# Sheet1.net
KiCad netlist of a schematic drawn in Altium Designer
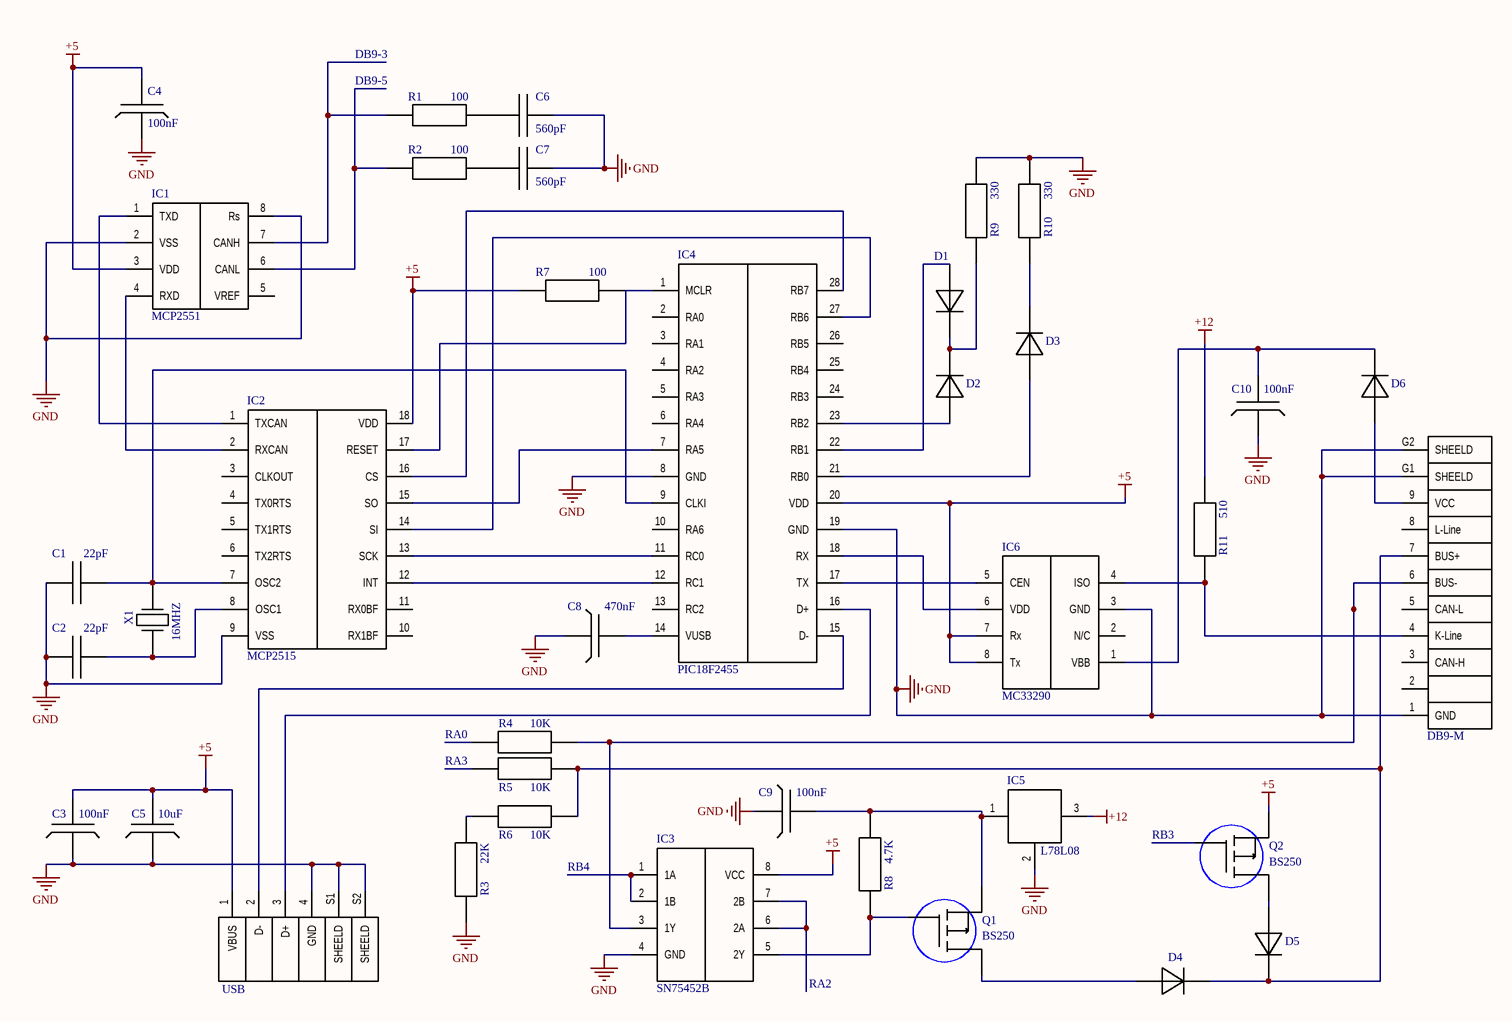
[diagram p0: Sheet1.SchDoc]

(export (version "E")
  (design (tool "Eeschema 10.0.6"))
  (components
    (comp (ref "C1")
      (value "22pF")
      (footprint "Miscellaneous Devices:C0805")
      (description "Capacitor")
      (fields (field (name "PUBLISHER") "Altium Limited"))
      (libsource (lib "PCB_Project") (part "Cap"))
    )
    (comp (ref "C2")
      (value "22pF")
      (footprint "Miscellaneous Devices:C0805")
      (description "Capacitor")
      (fields (field (name "PUBLISHER") "Altium Limited"))
      (libsource (lib "PCB_Project") (part "Cap"))
    )
    (comp (ref "C3")
      (value "100nF")
      (footprint "Miscellaneous Devices:C0805")
      (description "Capacitor with a designated external electrode")
      (fields (field (name "PUBLISHER") "Altium Limited"))
      (libsource (lib "PCB_Project") (part "Cap External"))
    )
    (comp (ref "C4")
      (value "100nF")
      (footprint "Miscellaneous Devices:C0805")
      (description "Capacitor with a designated external electrode")
      (fields (field (name "PUBLISHER") "Altium Limited"))
      (libsource (lib "PCB_Project") (part "Cap External"))
    )
    (comp (ref "C5")
      (value "10uF")
      (footprint "Miscellaneous Devices:C0805")
      (description "Capacitor with a designated external electrode")
      (fields (field (name "PUBLISHER") "Altium Limited"))
      (libsource (lib "PCB_Project") (part "Cap External"))
    )
    (comp (ref "C6")
      (value "560pF")
      (footprint "Miscellaneous Devices:C0805")
      (description "Capacitor")
      (fields (field (name "PUBLISHER") "Altium Limited"))
      (libsource (lib "PCB_Project") (part "Cap"))
    )
    (comp (ref "C7")
      (value "560pF")
      (footprint "Miscellaneous Devices:C0805")
      (description "Capacitor")
      (fields (field (name "PUBLISHER") "Altium Limited"))
      (libsource (lib "PCB_Project") (part "Cap"))
    )
    (comp (ref "C8")
      (value "470nF")
      (footprint "Miscellaneous Devices:C0805")
      (description "Capacitor with a designated external electrode")
      (fields (field (name "PUBLISHER") "Altium Limited"))
      (libsource (lib "PCB_Project") (part "Cap External"))
    )
    (comp (ref "C9")
      (value "100nF")
      (footprint "Miscellaneous Devices:C0805")
      (description "Capacitor with a designated external electrode")
      (fields (field (name "PUBLISHER") "Altium Limited"))
      (libsource (lib "PCB_Project") (part "Cap External"))
    )
    (comp (ref "C10")
      (value "100nF")
      (footprint "Miscellaneous Devices:C0805")
      (description "Capacitor with a designated external electrode")
      (fields (field (name "PUBLISHER") "Altium Limited"))
      (libsource (lib "PCB_Project") (part "Cap External"))
    )
    (comp (ref "D1")
      (value "Diode")
      (footprint "1N4148")
      (description "Default Diode")
      (fields (field (name "PUBLISHER") "Altium Limited"))
      (libsource (lib "PCB_Project") (part "Diode"))
    )
    (comp (ref "D2")
      (value "Diode")
      (footprint "1N4148")
      (description "Default Diode")
      (fields (field (name "PUBLISHER") "Altium Limited"))
      (libsource (lib "PCB_Project") (part "Diode"))
    )
    (comp (ref "D3")
      (value "Diode")
      (footprint "1N4148")
      (description "Default Diode")
      (fields (field (name "PUBLISHER") "Altium Limited"))
      (libsource (lib "PCB_Project") (part "Diode"))
    )
    (comp (ref "D4")
      (value "Diode")
      (footprint "1N4148")
      (description "Default Diode")
      (fields (field (name "PUBLISHER") "Altium Limited"))
      (libsource (lib "PCB_Project") (part "Diode"))
    )
    (comp (ref "D5")
      (value "Diode")
      (footprint "1N4148")
      (description "Default Diode")
      (fields (field (name "PUBLISHER") "Altium Limited"))
      (libsource (lib "PCB_Project") (part "Diode"))
    )
    (comp (ref "D6")
      (value "Diode")
      (footprint "1N4148")
      (description "Default Diode")
      (fields (field (name "PUBLISHER") "Altium Limited"))
      (libsource (lib "PCB_Project") (part "Diode"))
    )
    (comp (ref "IC1")
      (value "MCP2551")
      (footprint "SOIC127P599X175-8N")
      (fields (field (name "MP") "MCP2551-I/SN"))
      (libsource (lib "PCB_Project") (part "MCP2551-I/SN"))
    )
    (comp (ref "IC2")
      (value "MCP2515")
      (footprint "MCP2515")
      (description "CANbus Controller CAN 2.0 SPI Interface 18-SOIC")
      (fields (field (name "MP") "MCP2515-E/SO") (field (name "MF") "Microchip"))
      (libsource (lib "PCB_Project") (part "MCP2515-E/SO"))
    )
    (comp (ref "IC3")
      (value "SN75452B")
      (footprint "SOIC127P599X175-8N")
      (description "30-V Dual output driver with NAND logic inputs")
      (fields (field (name "MF") "Texas Instruments") (field (name "MP") "SN75452BD"))
      (libsource (lib "PCB_Project") (part "SN75452BD"))
    )
    (comp (ref "IC4")
      (value "PIC18F2455")
      (footprint "SOIC-SO28_N")
      (fields (field (name "PUBLISHER") "Altium Limited"))
      (libsource (lib "PCB_Project") (part "PIC18F2455-I/SO"))
    )
    (comp (ref "IC5")
      (value "L78L08")
      (footprint "L78L08")
      (description "Linear Voltage Regulator IC 1 Output 100mA SOT-89-3")
      (fields (field (name "MF") "STMicroelectronics") (field (name "MP") "L78L05ACU"))
      (libsource (lib "PCB_Project") (part "L78L05ACU"))
    )
    (comp (ref "IC6")
      (value "MC33290")
      (footprint "SO08:SO08")
      (fields (field (name "MF") "NXP USA"))
      (libsource (lib "PCB_Project") (part "MC33290"))
    )
    (comp (ref "P1")
      (value "USB")
      (footprint "USB-A1HSW6")
      (description "USB - A Receptacle Connector 4 Position Through Hole, Right Angle")
      (fields (field (name "MP") "USB-A1HSW6"))
      (libsource (lib "PCB_Project") (part "USB-A1HSW6"))
    )
    (comp (ref "P2") (value "DB9-M") (footprint "DB9") (libsource (lib "PCB_Project") (part "DB9-M")))
    (comp (ref "Q1")
      (value "BS250")
      (footprint "BS250FTA")
      (description "P-Channel 45V 90mA (Ta) 330mW (Ta) Surface Mount SOT-23-3")
      (fields (field (name "MF") "Diodes Inc.") (field (name "MP") "BS250FTA"))
      (libsource (lib "PCB_Project") (part "BS250FTA"))
    )
    (comp (ref "Q2")
      (value "BS250")
      (footprint "BS250FTA")
      (description "P-Channel 45V 90mA (Ta) 330mW (Ta) Surface Mount SOT-23-3")
      (fields (field (name "MF") "Diodes Inc.") (field (name "MP") "BS250FTA"))
      (libsource (lib "PCB_Project") (part "BS250FTA"))
    )
    (comp (ref "R1")
      (value "100")
      (footprint "Miscellaneous Devices:J1-0603")
      (description "Resistor")
      (fields (field (name "PUBLISHER") "Altium Limited"))
      (libsource (lib "PCB_Project") (part "Res3"))
    )
    (comp (ref "R2")
      (value "100")
      (footprint "Miscellaneous Devices:J1-0603")
      (description "Resistor")
      (fields (field (name "PUBLISHER") "Altium Limited"))
      (libsource (lib "PCB_Project") (part "Res3"))
    )
    (comp (ref "R3")
      (value "22K")
      (footprint "Miscellaneous Devices:J1-0603")
      (description "Resistor")
      (fields (field (name "PUBLISHER") "Altium Limited"))
      (libsource (lib "PCB_Project") (part "Res3"))
    )
    (comp (ref "R4")
      (value "10K")
      (footprint "Miscellaneous Devices:J1-0603")
      (description "Resistor")
      (fields (field (name "PUBLISHER") "Altium Limited"))
      (libsource (lib "PCB_Project") (part "Res3"))
    )
    (comp (ref "R5")
      (value "10K")
      (footprint "Miscellaneous Devices:J1-0603")
      (description "Resistor")
      (fields (field (name "PUBLISHER") "Altium Limited"))
      (libsource (lib "PCB_Project") (part "Res3"))
    )
    (comp (ref "R6")
      (value "10K")
      (footprint "Miscellaneous Devices:J1-0603")
      (description "Resistor")
      (fields (field (name "PUBLISHER") "Altium Limited"))
      (libsource (lib "PCB_Project") (part "Res3"))
    )
    (comp (ref "R7")
      (value "100")
      (footprint "Miscellaneous Devices:J1-0603")
      (description "Resistor")
      (fields (field (name "PUBLISHER") "Altium Limited"))
      (libsource (lib "PCB_Project") (part "Res3"))
    )
    (comp (ref "R8")
      (value "4.7K")
      (footprint "Miscellaneous Devices:J1-0603")
      (description "Resistor")
      (fields (field (name "PUBLISHER") "Altium Limited"))
      (libsource (lib "PCB_Project") (part "Res3"))
    )
    (comp (ref "R9")
      (value "330")
      (footprint "Miscellaneous Devices:J1-0603")
      (description "Resistor")
      (fields (field (name "PUBLISHER") "Altium Limited"))
      (libsource (lib "PCB_Project") (part "Res3"))
    )
    (comp (ref "R10")
      (value "330")
      (footprint "Miscellaneous Devices:J1-0603")
      (description "Resistor")
      (fields (field (name "PUBLISHER") "Altium Limited"))
      (libsource (lib "PCB_Project") (part "Res3"))
    )
    (comp (ref "R11")
      (value "510")
      (footprint "Miscellaneous Devices:J1-0603")
      (description "Resistor")
      (fields (field (name "PUBLISHER") "Altium Limited"))
      (libsource (lib "PCB_Project") (part "Res3"))
    )
    (comp (ref "X1")
      (value "16MHZ")
      (footprint "X-16.000MHZ-B4")
      (description "16 MHz Â±30ppm Crystal 18pF 40 Ohms HC-49/US")
      (fields (field (name "MP") "ABLS-16.000MHZ-B4") (field (name "MF") "Abracon"))
      (libsource (lib "PCB_Project") (part "ABLS-16.000MHZ-B4"))
    )
  )
  (nets
    (net (code "1") (name "+5") (class "Default")
      (node (ref "C3") (pin "1") (pinfunction "1_1") (pintype "passive"))
      (node (ref "C4") (pin "1") (pinfunction "1_1") (pintype "passive"))
      (node (ref "C5") (pin "1") (pinfunction "1_1") (pintype "passive"))
      (node (ref "IC1") (pin "3") (pinfunction "VDD_3") (pintype "power_in"))
      (node (ref "IC2") (pin "18") (pinfunction "VDD_18") (pintype "passive"))
      (node (ref "IC3") (pin "8") (pinfunction "VCC_8") (pintype "power_in"))
      (node (ref "IC4") (pin "20") (pinfunction "VDD_20") (pintype "power_in"))
      (node (ref "IC6") (pin "7") (pinfunction "Rx_7") (pintype "passive"))
      (node (ref "IC6") (pin "8") (pinfunction "Tx_8") (pintype "passive"))
      (node (ref "P1") (pin "1") (pinfunction "VBUS_1") (pintype "passive"))
      (node (ref "Q2") (pin "2") (pinfunction "S_2") (pintype "passive"))
      (node (ref "R7") (pin "1") (pinfunction "1_1") (pintype "passive"))
    )
    (net (code "2") (name "+12") (class "Default")
      (node (ref "IC5") (pin "3") (pinfunction "IN_3") (pintype "power_in"))
      (node (ref "R11") (pin "2") (pinfunction "2_2") (pintype "passive"))
    )
    (net (code "3") (name "GND") (class "Default")
      (node (ref "C1") (pin "1") (pinfunction "1_1") (pintype "passive"))
      (node (ref "C10") (pin "2") (pinfunction "2_2") (pintype "passive"))
      (node (ref "C2") (pin "1") (pinfunction "1_1") (pintype "passive"))
      (node (ref "C3") (pin "2") (pinfunction "2_2") (pintype "passive"))
      (node (ref "C4") (pin "2") (pinfunction "2_2") (pintype "passive"))
      (node (ref "C5") (pin "2") (pinfunction "2_2") (pintype "passive"))
      (node (ref "C6") (pin "2") (pinfunction "2_2") (pintype "passive"))
      (node (ref "C7") (pin "2") (pinfunction "2_2") (pintype "passive"))
      (node (ref "C8") (pin "2") (pinfunction "2_2") (pintype "passive"))
      (node (ref "C9") (pin "2") (pinfunction "2_2") (pintype "passive"))
      (node (ref "IC1") (pin "2") (pinfunction "VSS_2") (pintype "power_in"))
      (node (ref "IC1") (pin "8") (pinfunction "Rs_8") (pintype "passive"))
      (node (ref "IC2") (pin "9") (pinfunction "VSS_9") (pintype "power_in"))
      (node (ref "IC3") (pin "4") (pinfunction "GND_4") (pintype "power_in"))
      (node (ref "IC4") (pin "19") (pinfunction "GND_19") (pintype "power_in"))
      (node (ref "IC4") (pin "8") (pinfunction "GND_8") (pintype "power_in"))
      (node (ref "IC5") (pin "2") (pinfunction "GND_2") (pintype "power_in"))
      (node (ref "IC6") (pin "3") (pinfunction "GND_3") (pintype "power_in"))
      (node (ref "P1") (pin "4") (pinfunction "GND_4") (pintype "power_in"))
      (node (ref "P1") (pin "S1") (pinfunction "SHEELD_S1") (pintype "passive"))
      (node (ref "P1") (pin "S2") (pinfunction "SHEELD_S2") (pintype "passive"))
      (node (ref "P2") (pin "1") (pinfunction "GND_1") (pintype "passive"))
      (node (ref "P2") (pin "G1") (pinfunction "SHEELD_G1") (pintype "passive"))
      (node (ref "P2") (pin "G2") (pinfunction "SHEELD_G2") (pintype "passive"))
      (node (ref "R10") (pin "2") (pinfunction "2_2") (pintype "passive"))
      (node (ref "R3") (pin "1") (pinfunction "1_1") (pintype "passive"))
      (node (ref "R9") (pin "2") (pinfunction "2_2") (pintype "passive"))
    )
    (net (code "4") (name "Net-(C6-Pad1)") (class "Default")
      (node (ref "C6") (pin "1") (pinfunction "1_1") (pintype "passive"))
      (node (ref "R1") (pin "2") (pinfunction "2_2") (pintype "passive"))
    )
    (net (code "5") (name "Net-(C7-Pad1)") (class "Default")
      (node (ref "C7") (pin "1") (pinfunction "1_1") (pintype "passive"))
      (node (ref "R2") (pin "2") (pinfunction "2_2") (pintype "passive"))
    )
    (net (code "6") (name "Net-(D1-Pad2)") (class "Default")
      (node (ref "D1") (pin "2") (pinfunction "2_2") (pintype "passive"))
      (node (ref "D2") (pin "2") (pinfunction "2_2") (pintype "passive"))
      (node (ref "R9") (pin "1") (pinfunction "1_1") (pintype "passive"))
    )
    (net (code "7") (name "Net-(D3-Pad2)") (class "Default")
      (node (ref "D3") (pin "2") (pinfunction "2_2") (pintype "passive"))
      (node (ref "R10") (pin "1") (pinfunction "1_1") (pintype "passive"))
    )
    (net (code "8") (name "Net-(IC1-CANH)") (class "Default")
      (node (ref "IC1") (pin "7") (pinfunction "CANH_7") (pintype "passive"))
      (node (ref "R1") (pin "1") (pinfunction "1_1") (pintype "passive"))
    )
    (net (code "9") (name "Net-(IC1-CANL)") (class "Default")
      (node (ref "IC1") (pin "6") (pinfunction "CANL_6") (pintype "passive"))
      (node (ref "R2") (pin "1") (pinfunction "1_1") (pintype "passive"))
    )
    (net (code "10") (name "Net-(IC1-RXD)") (class "Default")
      (node (ref "IC1") (pin "4") (pinfunction "RXD_4") (pintype "passive"))
      (node (ref "IC2") (pin "2") (pinfunction "RXCAN_2") (pintype "passive"))
    )
    (net (code "11") (name "Net-(IC1-TXD)") (class "Default")
      (node (ref "IC1") (pin "1") (pinfunction "TXD_1") (pintype "passive"))
      (node (ref "IC2") (pin "1") (pinfunction "TXCAN_1") (pintype "passive"))
    )
    (net (code "12") (name "Net-(IC2-CS)") (class "Default")
      (node (ref "IC2") (pin "16") (pinfunction "CS_16") (pintype "passive"))
      (node (ref "IC4") (pin "28") (pinfunction "RB7_28") (pintype "passive"))
    )
    (net (code "13") (name "Net-(IC2-INT)") (class "Default")
      (node (ref "IC2") (pin "12") (pinfunction "INT_12") (pintype "passive"))
      (node (ref "IC4") (pin "12") (pinfunction "RC1_12") (pintype "passive"))
    )
    (net (code "14") (name "Net-(IC2-OSC1)") (class "Default")
      (node (ref "C2") (pin "2") (pinfunction "2_2") (pintype "passive"))
      (node (ref "IC2") (pin "8") (pinfunction "OSC1_8") (pintype "power_in"))
      (node (ref "X1") (pin "1") (pintype "passive"))
    )
    (net (code "15") (name "Net-(IC2-OSC2)") (class "Default")
      (node (ref "C1") (pin "2") (pinfunction "2_2") (pintype "passive"))
      (node (ref "IC2") (pin "7") (pinfunction "OSC2_7") (pintype "passive"))
      (node (ref "IC4") (pin "9") (pinfunction "CLKI_9") (pintype "passive"))
      (node (ref "X1") (pin "2") (pintype "passive"))
    )
    (net (code "16") (name "Net-(IC2-RESET)") (class "Default")
      (node (ref "IC2") (pin "17") (pinfunction "RESET_17") (pintype "passive"))
      (node (ref "IC4") (pin "1") (pinfunction "MCLR_1") (pintype "passive"))
      (node (ref "R7") (pin "2") (pinfunction "2_2") (pintype "passive"))
    )
    (net (code "17") (name "Net-(IC2-SCK)") (class "Default")
      (node (ref "IC2") (pin "13") (pinfunction "SCK_13") (pintype "passive"))
      (node (ref "IC4") (pin "11") (pinfunction "RC0_11") (pintype "passive"))
    )
    (net (code "18") (name "Net-(IC2-SI)") (class "Default")
      (node (ref "IC2") (pin "14") (pinfunction "SI_14") (pintype "passive"))
      (node (ref "IC4") (pin "27") (pinfunction "RB6_27") (pintype "passive"))
    )
    (net (code "19") (name "Net-(IC2-SO)") (class "Default")
      (node (ref "IC2") (pin "15") (pinfunction "SO_15") (pintype "passive"))
      (node (ref "IC4") (pin "7") (pinfunction "RA5_7") (pintype "passive"))
    )
    (net (code "20") (name "Net-(IC3-1A)") (class "Default")
      (node (ref "IC3") (pin "1") (pinfunction "1A_1") (pintype "passive"))
      (node (ref "IC3") (pin "2") (pinfunction "1B_2") (pintype "passive"))
    )
    (net (code "21") (name "Net-(IC3-1Y)") (class "Default")
      (node (ref "IC3") (pin "3") (pinfunction "1Y_3") (pintype "passive"))
      (node (ref "P2") (pin "6") (pinfunction "BUS-_6") (pintype "passive"))
      (node (ref "R4") (pin "2") (pinfunction "2_2") (pintype "passive"))
    )
    (net (code "22") (name "Net-(IC3-2A)") (class "Default")
      (node (ref "IC3") (pin "6") (pinfunction "2A_6") (pintype "passive"))
      (node (ref "IC3") (pin "7") (pinfunction "2B_7") (pintype "passive"))
    )
    (net (code "23") (name "Net-(IC3-2Y)") (class "Default")
      (node (ref "IC3") (pin "5") (pinfunction "2Y_5") (pintype "passive"))
      (node (ref "Q1") (pin "1") (pinfunction "G_1") (pintype "passive"))
      (node (ref "R8") (pin "1") (pinfunction "1_1") (pintype "passive"))
    )
    (net (code "24") (name "Net-(IC4-D+)") (class "Default")
      (node (ref "IC4") (pin "16") (pinfunction "D+_16") (pintype "passive"))
      (node (ref "P1") (pin "3") (pinfunction "D+_3") (pintype "passive"))
    )
    (net (code "25") (name "Net-(IC4-D-)") (class "Default")
      (node (ref "IC4") (pin "15") (pinfunction "D-_15") (pintype "passive"))
      (node (ref "P1") (pin "2") (pinfunction "D-_2") (pintype "passive"))
    )
    (net (code "26") (name "Net-(IC4-RB0)") (class "Default")
      (node (ref "D3") (pin "1") (pinfunction "1_1") (pintype "passive"))
      (node (ref "IC4") (pin "21") (pinfunction "RB0_21") (pintype "passive"))
    )
    (net (code "27") (name "Net-(IC4-RB1)") (class "Default")
      (node (ref "D1") (pin "1") (pinfunction "1_1") (pintype "passive"))
      (node (ref "IC4") (pin "22") (pinfunction "RB1_22") (pintype "passive"))
    )
    (net (code "28") (name "Net-(IC4-RB2)") (class "Default")
      (node (ref "D2") (pin "1") (pinfunction "1_1") (pintype "passive"))
      (node (ref "IC4") (pin "23") (pinfunction "RB2_23") (pintype "passive"))
    )
    (net (code "29") (name "Net-(IC4-RX)") (class "Default")
      (node (ref "IC4") (pin "18") (pinfunction "RX_18") (pintype "passive"))
      (node (ref "IC6") (pin "6") (pinfunction "VDD_6") (pintype "power_in"))
    )
    (net (code "30") (name "Net-(IC4-TX)") (class "Default")
      (node (ref "IC4") (pin "17") (pinfunction "TX_17") (pintype "passive"))
      (node (ref "IC6") (pin "5") (pinfunction "CEN_5") (pintype "passive"))
    )
    (net (code "31") (name "Net-(IC4-VUSB)") (class "Default")
      (node (ref "C8") (pin "1") (pinfunction "1_1") (pintype "passive"))
      (node (ref "IC4") (pin "14") (pinfunction "VUSB_14") (pintype "passive"))
    )
    (net (code "32") (name "Net-(IC5-OUT)") (class "Default")
      (node (ref "C9") (pin "1") (pinfunction "1_1") (pintype "passive"))
      (node (ref "IC5") (pin "1") (pinfunction "OUT_1") (pintype "power_in"))
      (node (ref "Q1") (pin "2") (pinfunction "S_2") (pintype "passive"))
      (node (ref "R8") (pin "2") (pinfunction "2_2") (pintype "passive"))
    )
    (net (code "33") (name "Net-(IC6-ISO)") (class "Default")
      (node (ref "IC6") (pin "4") (pinfunction "ISO_4") (pintype "passive"))
      (node (ref "P2") (pin "4") (pinfunction "K-Line_4") (pintype "passive"))
      (node (ref "R11") (pin "1") (pinfunction "1_1") (pintype "passive"))
    )
    (net (code "34") (name "Net-(IC6-VBB)") (class "Default")
      (node (ref "C10") (pin "1") (pinfunction "1_1") (pintype "passive"))
      (node (ref "D6") (pin "2") (pinfunction "2_2") (pintype "passive"))
      (node (ref "IC6") (pin "1") (pinfunction "VBB_1") (pintype "passive"))
    )
    (net (code "35") (name "Net-(P2-BUS+)") (class "Default")
      (node (ref "D4") (pin "2") (pinfunction "2_2") (pintype "passive"))
      (node (ref "D5") (pin "2") (pinfunction "2_2") (pintype "passive"))
      (node (ref "P2") (pin "7") (pinfunction "BUS+_7") (pintype "passive"))
      (node (ref "R5") (pin "2") (pinfunction "2_2") (pintype "passive"))
      (node (ref "R6") (pin "2") (pinfunction "2_2") (pintype "passive"))
    )
    (net (code "36") (name "Net-(P2-VCC)") (class "Default")
      (node (ref "D6") (pin "1") (pinfunction "1_1") (pintype "passive"))
      (node (ref "P2") (pin "9") (pinfunction "VCC_9") (pintype "passive"))
    )
    (net (code "37") (name "Net-(Q1-D)") (class "Default")
      (node (ref "D4") (pin "1") (pinfunction "1_1") (pintype "passive"))
      (node (ref "Q1") (pin "3") (pinfunction "D_3") (pintype "passive"))
    )
    (net (code "38") (name "Net-(Q2-D)") (class "Default")
      (node (ref "D5") (pin "1") (pinfunction "1_1") (pintype "passive"))
      (node (ref "Q2") (pin "3") (pinfunction "D_3") (pintype "passive"))
    )
    (net (code "39") (name "Net-(R3-Pad2)") (class "Default")
      (node (ref "R3") (pin "2") (pinfunction "2_2") (pintype "passive"))
      (node (ref "R6") (pin "1") (pinfunction "1_1") (pintype "passive"))
    )
    (net (code "40") (name "unconnected-(IC1-VREF-Pad5)") (class "Default")
      (node (ref "IC1") (pin "5") (pinfunction "VREF_5") (pintype "passive"))
    )
    (net (code "41") (name "unconnected-(IC2-CLKOUT-Pad3)") (class "Default")
      (node (ref "IC2") (pin "3") (pinfunction "CLKOUT_3") (pintype "passive"))
    )
    (net (code "42") (name "unconnected-(IC2-RX0BF-Pad11)") (class "Default")
      (node (ref "IC2") (pin "11") (pinfunction "RX0BF_11") (pintype "passive"))
    )
    (net (code "43") (name "unconnected-(IC2-RX1BF-Pad10)") (class "Default")
      (node (ref "IC2") (pin "10") (pinfunction "RX1BF_10") (pintype "passive"))
    )
    (net (code "44") (name "unconnected-(IC2-TX0RTS-Pad4)") (class "Default")
      (node (ref "IC2") (pin "4") (pinfunction "TX0RTS_4") (pintype "passive"))
    )
    (net (code "45") (name "unconnected-(IC2-TX1RTS-Pad5)") (class "Default")
      (node (ref "IC2") (pin "5") (pinfunction "TX1RTS_5") (pintype "passive"))
    )
    (net (code "46") (name "unconnected-(IC2-TX2RTS-Pad6)") (class "Default")
      (node (ref "IC2") (pin "6") (pinfunction "TX2RTS_6") (pintype "passive"))
    )
    (net (code "47") (name "unconnected-(IC4-RA0-Pad2)") (class "Default")
      (node (ref "IC4") (pin "2") (pinfunction "RA0_2") (pintype "passive"))
    )
    (net (code "48") (name "unconnected-(IC4-RA1-Pad3)") (class "Default")
      (node (ref "IC4") (pin "3") (pinfunction "RA1_3") (pintype "passive"))
    )
    (net (code "49") (name "unconnected-(IC4-RA2-Pad4)") (class "Default")
      (node (ref "IC4") (pin "4") (pinfunction "RA2_4") (pintype "passive"))
    )
    (net (code "50") (name "unconnected-(IC4-RA3-Pad5)") (class "Default")
      (node (ref "IC4") (pin "5") (pinfunction "RA3_5") (pintype "passive"))
    )
    (net (code "51") (name "unconnected-(IC4-RA4-Pad6)") (class "Default")
      (node (ref "IC4") (pin "6") (pinfunction "RA4_6") (pintype "passive"))
    )
    (net (code "52") (name "unconnected-(IC4-RA6-Pad10)") (class "Default")
      (node (ref "IC4") (pin "10") (pinfunction "RA6_10") (pintype "passive"))
    )
    (net (code "53") (name "unconnected-(IC4-RB3-Pad24)") (class "Default")
      (node (ref "IC4") (pin "24") (pinfunction "RB3_24") (pintype "passive"))
    )
    (net (code "54") (name "unconnected-(IC4-RB4-Pad25)") (class "Default")
      (node (ref "IC4") (pin "25") (pinfunction "RB4_25") (pintype "passive"))
    )
    (net (code "55") (name "unconnected-(IC4-RB5-Pad26)") (class "Default")
      (node (ref "IC4") (pin "26") (pinfunction "RB5_26") (pintype "passive"))
    )
    (net (code "56") (name "unconnected-(IC4-RC2-Pad13)") (class "Default")
      (node (ref "IC4") (pin "13") (pinfunction "RC2_13") (pintype "passive"))
    )
    (net (code "57") (name "unconnected-(IC6-N{slash}C-Pad2)") (class "Default")
      (node (ref "IC6") (pin "2") (pinfunction "N/C_2") (pintype "passive"))
    )
    (net (code "58") (name "unconnected-(P2-CAN-H-Pad3)") (class "Default")
      (node (ref "P2") (pin "3") (pinfunction "CAN-H_3") (pintype "passive"))
    )
    (net (code "59") (name "unconnected-(P2-CAN-L-Pad5)") (class "Default")
      (node (ref "P2") (pin "5") (pinfunction "CAN-L_5") (pintype "passive"))
    )
    (net (code "60") (name "unconnected-(P2-L-Line-Pad8)") (class "Default")
      (node (ref "P2") (pin "8") (pinfunction "L-Line_8") (pintype "passive"))
    )
    (net (code "61") (name "unconnected-(P2-Pad2)") (class "Default")
      (node (ref "P2") (pin "2") (pintype "passive"))
    )
    (net (code "62") (name "unconnected-(Q2-G-Pad1)") (class "Default")
      (node (ref "Q2") (pin "1") (pinfunction "G_1") (pintype "passive"))
    )
    (net (code "63") (name "unconnected-(R4-Pad1)") (class "Default")
      (node (ref "R4") (pin "1") (pinfunction "1_1") (pintype "passive"))
    )
    (net (code "64") (name "unconnected-(R5-Pad1)") (class "Default")
      (node (ref "R5") (pin "1") (pinfunction "1_1") (pintype "passive"))
    )
  )
)
